# master-pcb.net
KiCad netlist of a schematic drawn in Altium Designer
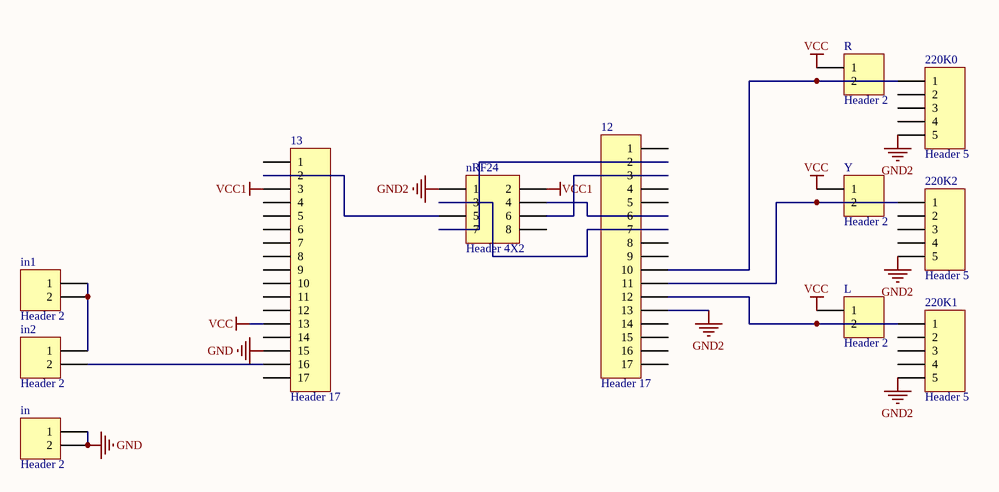
[diagram p0: master-pcb.SchDoc]

(export (version "E")
  (design (tool "Eeschema 10.0.6"))
  (components
    (comp (ref "12")
      (value "Header 17")
      (footprint "HDR1X17")
      (description "Header, 17-Pin")
      (fields (field (name "PUBLISHER") "Altium Limited"))
      (libsource (lib "Miscellaneous Connectors") (part "Header 17"))
    )
    (comp (ref "13")
      (value "Header 17")
      (footprint "HDR1X17")
      (description "Header, 17-Pin")
      (fields (field (name "PUBLISHER") "Altium Limited"))
      (libsource (lib "") (part "Header 17_1"))
    )
    (comp (ref "220K0")
      (value "Header 5")
      (footprint "HDR1X5")
      (description "Header, 5-Pin")
      (fields (field (name "PUBLISHER") "Altium Limited"))
      (libsource (lib "Miscellaneous Connectors") (part "Header 5"))
    )
    (comp (ref "220K1")
      (value "Header 5")
      (footprint "HDR1X5")
      (description "Header, 5-Pin")
      (fields (field (name "PUBLISHER") "Altium Limited"))
      (libsource (lib "Miscellaneous Connectors") (part "Header 5"))
    )
    (comp (ref "220K2")
      (value "Header 5")
      (footprint "HDR1X5")
      (description "Header, 5-Pin")
      (fields (field (name "PUBLISHER") "Altium Limited"))
      (libsource (lib "Miscellaneous Connectors") (part "Header 5"))
    )
    (comp (ref "in")
      (value "Header 2")
      (footprint "HDR1X2")
      (description "Header, 2-Pin")
      (fields (field (name "PUBLISHER") "Altium Limited"))
      (libsource (lib "Miscellaneous Connectors") (part "Header 2"))
    )
    (comp (ref "in1")
      (value "Header 2")
      (footprint "HDR1X2")
      (description "Header, 2-Pin")
      (fields (field (name "PUBLISHER") "Altium Limited"))
      (libsource (lib "Miscellaneous Connectors") (part "Header 2"))
    )
    (comp (ref "in2")
      (value "Header 2")
      (footprint "HDR1X2")
      (description "Header, 2-Pin")
      (fields (field (name "PUBLISHER") "Altium Limited"))
      (libsource (lib "Miscellaneous Connectors") (part "Header 2"))
    )
    (comp (ref "L")
      (value "Header 2")
      (footprint "HDR1X2")
      (description "Header, 2-Pin")
      (fields (field (name "PUBLISHER") "Altium Limited"))
      (libsource (lib "") (part "Header 2_1"))
    )
    (comp (ref "nRF24")
      (value "Header 4X2")
      (footprint "HDR2X4")
      (description "Header, 4-Pin, Dual row")
      (fields (field (name "PUBLISHER") "Altium Limited"))
      (libsource (lib "Miscellaneous Connectors") (part "Header 4X2"))
    )
    (comp (ref "R")
      (value "Header 2")
      (footprint "HDR1X2")
      (description "Header, 2-Pin")
      (fields (field (name "PUBLISHER") "Altium Limited"))
      (libsource (lib "") (part "Header 2_1"))
    )
    (comp (ref "Y")
      (value "Header 2")
      (footprint "HDR1X2")
      (description "Header, 2-Pin")
      (fields (field (name "PUBLISHER") "Altium Limited"))
      (libsource (lib "") (part "Header 2_1"))
    )
  )
  (nets
    (net (code "1") (name "GND") (class "Default")
      (node (ref "13") (pin "15") (pinfunction "15_15") (pintype "passive"))
      (node (ref "in") (pin "1") (pinfunction "1_1") (pintype "passive"))
      (node (ref "in") (pin "2") (pinfunction "2_2") (pintype "passive"))
    )
    (net (code "2") (name "GND2") (class "Default")
      (node (ref "12") (pin "13") (pinfunction "13_13") (pintype "passive"))
      (node (ref "220K0") (pin "5") (pinfunction "5_5") (pintype "passive"))
      (node (ref "220K1") (pin "5") (pinfunction "5_5") (pintype "passive"))
      (node (ref "220K2") (pin "5") (pinfunction "5_5") (pintype "passive"))
      (node (ref "nRF24") (pin "1") (pinfunction "1_1") (pintype "passive"))
    )
    (net (code "3") (name "Net-(12-Pad2)") (class "Default")
      (node (ref "12") (pin "2") (pinfunction "2_2") (pintype "passive"))
      (node (ref "nRF24") (pin "7") (pinfunction "7_7") (pintype "passive"))
    )
    (net (code "4") (name "Net-(12-Pad3)") (class "Default")
      (node (ref "12") (pin "3") (pinfunction "3_3") (pintype "passive"))
      (node (ref "nRF24") (pin "6") (pinfunction "6_6") (pintype "passive"))
    )
    (net (code "5") (name "Net-(12-Pad6)") (class "Default")
      (node (ref "12") (pin "6") (pinfunction "6_6") (pintype "passive"))
      (node (ref "nRF24") (pin "4") (pinfunction "4_4") (pintype "passive"))
    )
    (net (code "6") (name "Net-(12-Pad7)") (class "Default")
      (node (ref "12") (pin "7") (pinfunction "7_7") (pintype "passive"))
      (node (ref "nRF24") (pin "3") (pinfunction "3_3") (pintype "passive"))
    )
    (net (code "7") (name "Net-(12-Pad10)") (class "Default")
      (node (ref "12") (pin "10") (pinfunction "10_10") (pintype "passive"))
      (node (ref "220K0") (pin "1") (pinfunction "1_1") (pintype "passive"))
      (node (ref "R") (pin "2") (pinfunction "2_2") (pintype "passive"))
    )
    (net (code "8") (name "Net-(12-Pad11)") (class "Default")
      (node (ref "12") (pin "11") (pinfunction "11_11") (pintype "passive"))
      (node (ref "220K2") (pin "1") (pinfunction "1_1") (pintype "passive"))
      (node (ref "Y") (pin "2") (pinfunction "2_2") (pintype "passive"))
    )
    (net (code "9") (name "Net-(12-Pad12)") (class "Default")
      (node (ref "12") (pin "12") (pinfunction "12_12") (pintype "passive"))
      (node (ref "220K1") (pin "1") (pinfunction "1_1") (pintype "passive"))
      (node (ref "L") (pin "2") (pinfunction "2_2") (pintype "passive"))
    )
    (net (code "10") (name "Net-(13-Pad2)") (class "Default")
      (node (ref "13") (pin "2") (pinfunction "2_2") (pintype "passive"))
      (node (ref "nRF24") (pin "5") (pinfunction "5_5") (pintype "passive"))
    )
    (net (code "11") (name "Net-(13-Pad16)") (class "Default")
      (node (ref "13") (pin "16") (pinfunction "16_16") (pintype "passive"))
      (node (ref "in2") (pin "2") (pinfunction "2_2") (pintype "passive"))
    )
    (net (code "12") (name "Net-(in1-Pad1)") (class "Default")
      (node (ref "in1") (pin "1") (pinfunction "1_1") (pintype "passive"))
      (node (ref "in1") (pin "2") (pinfunction "2_2") (pintype "passive"))
      (node (ref "in2") (pin "1") (pinfunction "1_1") (pintype "passive"))
    )
    (net (code "13") (name "VCC") (class "Default")
      (node (ref "13") (pin "13") (pinfunction "13_13") (pintype "passive"))
      (node (ref "L") (pin "1") (pinfunction "1_1") (pintype "passive"))
      (node (ref "R") (pin "1") (pinfunction "1_1") (pintype "passive"))
      (node (ref "Y") (pin "1") (pinfunction "1_1") (pintype "passive"))
    )
    (net (code "14") (name "VCC1") (class "Default")
      (node (ref "13") (pin "3") (pinfunction "3_3") (pintype "passive"))
      (node (ref "nRF24") (pin "2") (pinfunction "2_2") (pintype "passive"))
    )
    (net (code "15") (name "unconnected-(12-Pad1)") (class "Default")
      (node (ref "12") (pin "1") (pinfunction "1_1") (pintype "passive"))
    )
    (net (code "16") (name "unconnected-(12-Pad4)") (class "Default")
      (node (ref "12") (pin "4") (pinfunction "4_4") (pintype "passive"))
    )
    (net (code "17") (name "unconnected-(12-Pad5)") (class "Default")
      (node (ref "12") (pin "5") (pinfunction "5_5") (pintype "passive"))
    )
    (net (code "18") (name "unconnected-(12-Pad8)") (class "Default")
      (node (ref "12") (pin "8") (pinfunction "8_8") (pintype "passive"))
    )
    (net (code "19") (name "unconnected-(12-Pad9)") (class "Default")
      (node (ref "12") (pin "9") (pinfunction "9_9") (pintype "passive"))
    )
    (net (code "20") (name "unconnected-(12-Pad14)") (class "Default")
      (node (ref "12") (pin "14") (pinfunction "14_14") (pintype "passive"))
    )
    (net (code "21") (name "unconnected-(12-Pad15)") (class "Default")
      (node (ref "12") (pin "15") (pinfunction "15_15") (pintype "passive"))
    )
    (net (code "22") (name "unconnected-(12-Pad16)") (class "Default")
      (node (ref "12") (pin "16") (pinfunction "16_16") (pintype "passive"))
    )
    (net (code "23") (name "unconnected-(12-Pad17)") (class "Default")
      (node (ref "12") (pin "17") (pinfunction "17_17") (pintype "passive"))
    )
    (net (code "24") (name "unconnected-(13-Pad1)") (class "Default")
      (node (ref "13") (pin "1") (pinfunction "1_1") (pintype "passive"))
    )
    (net (code "25") (name "unconnected-(13-Pad4)") (class "Default")
      (node (ref "13") (pin "4") (pinfunction "4_4") (pintype "passive"))
    )
    (net (code "26") (name "unconnected-(13-Pad5)") (class "Default")
      (node (ref "13") (pin "5") (pinfunction "5_5") (pintype "passive"))
    )
    (net (code "27") (name "unconnected-(13-Pad6)") (class "Default")
      (node (ref "13") (pin "6") (pinfunction "6_6") (pintype "passive"))
    )
    (net (code "28") (name "unconnected-(13-Pad7)") (class "Default")
      (node (ref "13") (pin "7") (pinfunction "7_7") (pintype "passive"))
    )
    (net (code "29") (name "unconnected-(13-Pad8)") (class "Default")
      (node (ref "13") (pin "8") (pinfunction "8_8") (pintype "passive"))
    )
    (net (code "30") (name "unconnected-(13-Pad9)") (class "Default")
      (node (ref "13") (pin "9") (pinfunction "9_9") (pintype "passive"))
    )
    (net (code "31") (name "unconnected-(13-Pad10)") (class "Default")
      (node (ref "13") (pin "10") (pinfunction "10_10") (pintype "passive"))
    )
    (net (code "32") (name "unconnected-(13-Pad11)") (class "Default")
      (node (ref "13") (pin "11") (pinfunction "11_11") (pintype "passive"))
    )
    (net (code "33") (name "unconnected-(13-Pad12)") (class "Default")
      (node (ref "13") (pin "12") (pinfunction "12_12") (pintype "passive"))
    )
    (net (code "34") (name "unconnected-(13-Pad14)") (class "Default")
      (node (ref "13") (pin "14") (pinfunction "14_14") (pintype "passive"))
    )
    (net (code "35") (name "unconnected-(13-Pad17)") (class "Default")
      (node (ref "13") (pin "17") (pinfunction "17_17") (pintype "passive"))
    )
    (net (code "36") (name "unconnected-(220K0-Pad2)") (class "Default")
      (node (ref "220K0") (pin "2") (pinfunction "2_2") (pintype "passive"))
    )
    (net (code "37") (name "unconnected-(220K0-Pad3)") (class "Default")
      (node (ref "220K0") (pin "3") (pinfunction "3_3") (pintype "passive"))
    )
    (net (code "38") (name "unconnected-(220K0-Pad4)") (class "Default")
      (node (ref "220K0") (pin "4") (pinfunction "4_4") (pintype "passive"))
    )
    (net (code "39") (name "unconnected-(220K1-Pad2)") (class "Default")
      (node (ref "220K1") (pin "2") (pinfunction "2_2") (pintype "passive"))
    )
    (net (code "40") (name "unconnected-(220K1-Pad3)") (class "Default")
      (node (ref "220K1") (pin "3") (pinfunction "3_3") (pintype "passive"))
    )
    (net (code "41") (name "unconnected-(220K1-Pad4)") (class "Default")
      (node (ref "220K1") (pin "4") (pinfunction "4_4") (pintype "passive"))
    )
    (net (code "42") (name "unconnected-(220K2-Pad2)") (class "Default")
      (node (ref "220K2") (pin "2") (pinfunction "2_2") (pintype "passive"))
    )
    (net (code "43") (name "unconnected-(220K2-Pad3)") (class "Default")
      (node (ref "220K2") (pin "3") (pinfunction "3_3") (pintype "passive"))
    )
    (net (code "44") (name "unconnected-(220K2-Pad4)") (class "Default")
      (node (ref "220K2") (pin "4") (pinfunction "4_4") (pintype "passive"))
    )
    (net (code "45") (name "unconnected-(nRF24-Pad8)") (class "Default")
      (node (ref "nRF24") (pin "8") (pinfunction "8_8") (pintype "passive"))
    )
  )
)
